# PCB.net
KiCad netlist of a schematic drawn in EAGLE
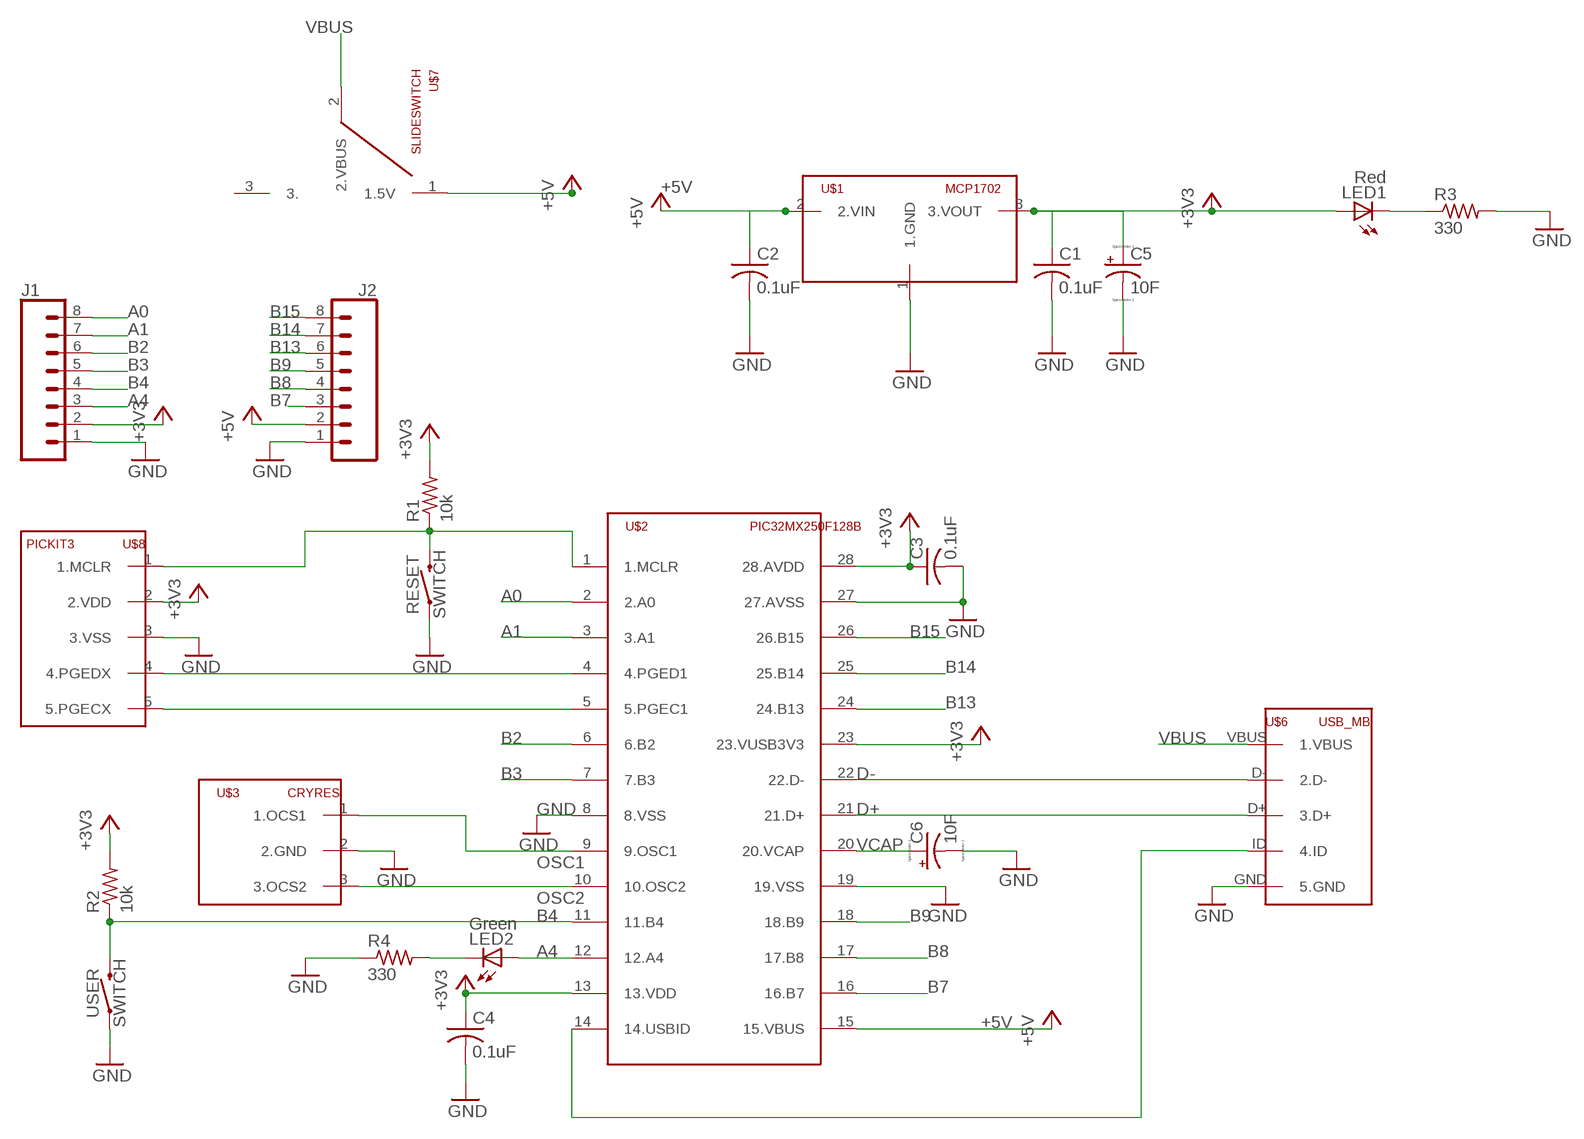
[diagram p0: schematic, sheet 1]

(export (version "E")
  (design (tool "Eeschema 10.0.6"))
  (components
    (comp (ref "C1")
      (value "0.1uF")
      (footprint "eagle-import:C025-025X050")
      (libsource (lib "eagle-import") (part "C-US025-025X050"))
    )
    (comp (ref "C2")
      (value "0.1uF")
      (footprint "eagle-import:C025-025X050")
      (libsource (lib "eagle-import") (part "C-US025-025X050"))
    )
    (comp (ref "C3")
      (value "0.1uF")
      (footprint "eagle-import:C025-025X050")
      (libsource (lib "eagle-import") (part "C-US025-025X050"))
    )
    (comp (ref "C4")
      (value "0.1uF")
      (footprint "eagle-import:C025-025X050")
      (libsource (lib "eagle-import") (part "C-US025-025X050"))
    )
    (comp (ref "C5")
      (value "10F")
      (footprint "eagle-import:E5-5")
      (libsource (lib "eagle-import") (part "CPOL-USE5-5"))
    )
    (comp (ref "C6")
      (value "10F")
      (footprint "eagle-import:E5-5")
      (libsource (lib "eagle-import") (part "CPOL-USE5-5"))
    )
    (comp (ref "J1")
      (value "CONN_08\"")
      (footprint "eagle-import:1X08")
      (libsource (lib "eagle-import") (part "CONN_08{dblquote}"))
    )
    (comp (ref "J2")
      (value "CONN_08\"")
      (footprint "eagle-import:1X08")
      (libsource (lib "eagle-import") (part "CONN_08{dblquote}"))
    )
    (comp (ref "LED1")
      (value "Red")
      (footprint "eagle-import:LED3MM")
      (libsource (lib "eagle-import") (part "LED3MM"))
    )
    (comp (ref "LED2")
      (value "Green")
      (footprint "eagle-import:LED3MM")
      (libsource (lib "eagle-import") (part "LED3MM"))
    )
    (comp (ref "R1")
      (value "10k")
      (footprint "eagle-import:0207_10")
      (libsource (lib "eagle-import") (part "R-US_0207/10"))
    )
    (comp (ref "R2")
      (value "10k")
      (footprint "eagle-import:0207_10")
      (libsource (lib "eagle-import") (part "R-US_0207/10"))
    )
    (comp (ref "R3")
      (value "330")
      (footprint "eagle-import:0207_10")
      (libsource (lib "eagle-import") (part "R-US_0207/10"))
    )
    (comp (ref "R4")
      (value "330")
      (footprint "eagle-import:0207_10")
      (libsource (lib "eagle-import") (part "R-US_0207/10"))
    )
    (comp (ref "RESET")
      (value "SWITCH")
      (footprint "eagle-import:SWITCH")
      (libsource (lib "eagle-import") (part "SWITCH"))
    )
    (comp (ref "U$1")
      (value "MCP1702")
      (footprint "eagle-import:TO92")
      (libsource (lib "eagle-import") (part "MCP1702"))
    )
    (comp (ref "U$2")
      (value "PIC32MX250F128B")
      (footprint "eagle-import:DIL28-3")
      (libsource (lib "eagle-import") (part "PIC32MX250F128B"))
    )
    (comp (ref "U$3")
      (value "CRYRES")
      (footprint "eagle-import:CRYSTAL")
      (libsource (lib "eagle-import") (part "CRYRES"))
    )
    (comp (ref "U$6")
      (value "USB_MB")
      (footprint "eagle-import:USB-MB-H")
      (libsource (lib "eagle-import") (part "USB_MB"))
    )
    (comp (ref "U$7")
      (value "SLIDESWITCH")
      (footprint "eagle-import:SLIDESWITCH")
      (libsource (lib "eagle-import") (part "SLIDESWITCH"))
    )
    (comp (ref "U$8")
      (value "PICKIT3")
      (footprint "eagle-import:1X05")
      (libsource (lib "eagle-import") (part "PICKIT3"))
    )
    (comp (ref "USER")
      (value "SWITCH")
      (footprint "eagle-import:SWITCH")
      (libsource (lib "eagle-import") (part "SWITCH"))
    )
  )
  (nets
    (net (code "1") (name "+3V3") (class "Default")
      (node (ref "C1") (pin "1") (pinfunction "1_1") (pintype "passive"))
      (node (ref "C3") (pin "1") (pinfunction "1_1") (pintype "passive"))
      (node (ref "C4") (pin "1") (pinfunction "1_1") (pintype "passive"))
      (node (ref "C5") (pin "+") (pinfunction "+_+") (pintype "passive"))
      (node (ref "J1") (pin "2") (pinfunction "2_2") (pintype "passive"))
      (node (ref "LED1") (pin "A") (pinfunction "A_A") (pintype "passive"))
      (node (ref "R1") (pin "2") (pinfunction "2_2") (pintype "passive"))
      (node (ref "R2") (pin "2") (pinfunction "2_2") (pintype "passive"))
      (node (ref "U$1") (pin "3") (pinfunction "3.VOUT_3") (pintype "bidirectional"))
      (node (ref "U$2") (pin "13") (pinfunction "13.VDD_13") (pintype "bidirectional"))
      (node (ref "U$2") (pin "23") (pinfunction "23.VUSB3V3_23") (pintype "bidirectional"))
      (node (ref "U$2") (pin "28") (pinfunction "28.AVDD_28") (pintype "bidirectional"))
      (node (ref "U$8") (pin "2") (pinfunction "2.VDD_2") (pintype "bidirectional"))
    )
    (net (code "2") (name "+5V") (class "Default")
      (node (ref "C2") (pin "1") (pinfunction "1_1") (pintype "passive"))
      (node (ref "J2") (pin "2") (pinfunction "2_2") (pintype "passive"))
      (node (ref "U$1") (pin "2") (pinfunction "2.VIN_2") (pintype "bidirectional"))
      (node (ref "U$2") (pin "15") (pinfunction "15.VBUS_15") (pintype "bidirectional"))
      (node (ref "U$7") (pin "1") (pinfunction "1.5V_1") (pintype "bidirectional"))
    )
    (net (code "3") (name "/A0") (class "Default")
      (node (ref "J1") (pin "8") (pinfunction "8_8") (pintype "passive"))
      (node (ref "U$2") (pin "2") (pinfunction "2.A0_2") (pintype "bidirectional"))
    )
    (net (code "4") (name "/A1") (class "Default")
      (node (ref "J1") (pin "7") (pinfunction "7_7") (pintype "passive"))
      (node (ref "U$2") (pin "3") (pinfunction "3.A1_3") (pintype "bidirectional"))
    )
    (net (code "5") (name "/A4") (class "Default")
      (node (ref "J1") (pin "3") (pinfunction "3_3") (pintype "passive"))
      (node (ref "LED2") (pin "A") (pinfunction "A_A") (pintype "passive"))
      (node (ref "U$2") (pin "12") (pinfunction "12.A4_12") (pintype "bidirectional"))
    )
    (net (code "6") (name "/B2") (class "Default")
      (node (ref "J1") (pin "6") (pinfunction "6_6") (pintype "passive"))
      (node (ref "U$2") (pin "6") (pinfunction "6.B2_6") (pintype "bidirectional"))
    )
    (net (code "7") (name "/B3") (class "Default")
      (node (ref "J1") (pin "5") (pinfunction "5_5") (pintype "passive"))
      (node (ref "U$2") (pin "7") (pinfunction "7.B3_7") (pintype "bidirectional"))
    )
    (net (code "8") (name "/B4") (class "Default")
      (node (ref "J1") (pin "4") (pinfunction "4_4") (pintype "passive"))
      (node (ref "R2") (pin "1") (pinfunction "1_1") (pintype "passive"))
      (node (ref "U$2") (pin "11") (pinfunction "11.B4_11") (pintype "bidirectional"))
      (node (ref "USER") (pin "2") (pinfunction "2_2") (pintype "passive"))
    )
    (net (code "9") (name "/B7") (class "Default")
      (node (ref "J2") (pin "3") (pinfunction "3_3") (pintype "passive"))
      (node (ref "U$2") (pin "16") (pinfunction "16.B7_16") (pintype "bidirectional"))
    )
    (net (code "10") (name "/B8") (class "Default")
      (node (ref "J2") (pin "4") (pinfunction "4_4") (pintype "passive"))
      (node (ref "U$2") (pin "17") (pinfunction "17.B8_17") (pintype "bidirectional"))
    )
    (net (code "11") (name "/B9") (class "Default")
      (node (ref "J2") (pin "5") (pinfunction "5_5") (pintype "passive"))
      (node (ref "U$2") (pin "18") (pinfunction "18.B9_18") (pintype "bidirectional"))
    )
    (net (code "12") (name "/B13") (class "Default")
      (node (ref "J2") (pin "6") (pinfunction "6_6") (pintype "passive"))
      (node (ref "U$2") (pin "24") (pinfunction "24.B13_24") (pintype "bidirectional"))
    )
    (net (code "13") (name "/B14") (class "Default")
      (node (ref "J2") (pin "7") (pinfunction "7_7") (pintype "passive"))
      (node (ref "U$2") (pin "25") (pinfunction "25.B14_25") (pintype "bidirectional"))
    )
    (net (code "14") (name "/B15") (class "Default")
      (node (ref "J2") (pin "8") (pinfunction "8_8") (pintype "passive"))
      (node (ref "U$2") (pin "26") (pinfunction "26.B15_26") (pintype "bidirectional"))
    )
    (net (code "15") (name "/D+") (class "Default")
      (node (ref "U$2") (pin "21") (pinfunction "21.D+_21") (pintype "bidirectional"))
      (node (ref "U$6") (pin "D+") (pinfunction "3.D+_D+") (pintype "bidirectional"))
    )
    (net (code "16") (name "/D-") (class "Default")
      (node (ref "U$2") (pin "22") (pinfunction "22.D-_22") (pintype "bidirectional"))
      (node (ref "U$6") (pin "D-") (pinfunction "2.D-_D-") (pintype "bidirectional"))
    )
    (net (code "17") (name "/OSC1") (class "Default")
      (node (ref "U$2") (pin "9") (pinfunction "9.OSC1_9") (pintype "bidirectional"))
      (node (ref "U$3") (pin "1") (pinfunction "1.OCS1_1") (pintype "bidirectional"))
    )
    (net (code "18") (name "/OSC2") (class "Default")
      (node (ref "U$2") (pin "10") (pinfunction "10.OSC2_10") (pintype "bidirectional"))
      (node (ref "U$3") (pin "3") (pinfunction "3.OCS2_3") (pintype "bidirectional"))
    )
    (net (code "19") (name "/VBUS") (class "Default")
      (node (ref "U$6") (pin "VBUS") (pinfunction "1.VBUS_VBUS") (pintype "bidirectional"))
      (node (ref "U$7") (pin "2") (pinfunction "2.VBUS_2") (pintype "bidirectional"))
    )
    (net (code "20") (name "/VCAP") (class "Default")
      (node (ref "C6") (pin "+") (pinfunction "+_+") (pintype "passive"))
      (node (ref "U$2") (pin "20") (pinfunction "20.VCAP_20") (pintype "bidirectional"))
    )
    (net (code "21") (name "GND") (class "Default")
      (node (ref "C1") (pin "2") (pinfunction "2_2") (pintype "passive"))
      (node (ref "C2") (pin "2") (pinfunction "2_2") (pintype "passive"))
      (node (ref "C3") (pin "2") (pinfunction "2_2") (pintype "passive"))
      (node (ref "C4") (pin "2") (pinfunction "2_2") (pintype "passive"))
      (node (ref "C5") (pin "-") (pinfunction "-_-") (pintype "passive"))
      (node (ref "C6") (pin "-") (pinfunction "-_-") (pintype "passive"))
      (node (ref "J1") (pin "1") (pinfunction "1_1") (pintype "passive"))
      (node (ref "J2") (pin "1") (pinfunction "1_1") (pintype "passive"))
      (node (ref "R3") (pin "2") (pinfunction "2_2") (pintype "passive"))
      (node (ref "R4") (pin "1") (pinfunction "1_1") (pintype "passive"))
      (node (ref "RESET") (pin "1") (pinfunction "1_1") (pintype "passive"))
      (node (ref "U$1") (pin "1") (pinfunction "1.GND_1") (pintype "bidirectional"))
      (node (ref "U$2") (pin "19") (pinfunction "19.VSS_19") (pintype "bidirectional"))
      (node (ref "U$2") (pin "27") (pinfunction "27.AVSS_27") (pintype "bidirectional"))
      (node (ref "U$2") (pin "8") (pinfunction "8.VSS_8") (pintype "bidirectional"))
      (node (ref "U$3") (pin "2") (pinfunction "2.GND_2") (pintype "bidirectional"))
      (node (ref "U$6") (pin "GND") (pinfunction "5.GND_GND") (pintype "bidirectional"))
      (node (ref "U$8") (pin "3") (pinfunction "3.VSS_3") (pintype "bidirectional"))
      (node (ref "USER") (pin "1") (pinfunction "1_1") (pintype "passive"))
    )
    (net (code "22") (name "Net-(LED1-C)") (class "Default")
      (node (ref "LED1") (pin "K") (pinfunction "C_K") (pintype "passive"))
      (node (ref "R3") (pin "1") (pinfunction "1_1") (pintype "passive"))
    )
    (net (code "23") (name "Net-(LED2-C)") (class "Default")
      (node (ref "LED2") (pin "K") (pinfunction "C_K") (pintype "passive"))
      (node (ref "R4") (pin "2") (pinfunction "2_2") (pintype "passive"))
    )
    (net (code "24") (name "Net-(U$2-1.MCLR)") (class "Default")
      (node (ref "R1") (pin "1") (pinfunction "1_1") (pintype "passive"))
      (node (ref "RESET") (pin "2") (pinfunction "2_2") (pintype "passive"))
      (node (ref "U$2") (pin "1") (pinfunction "1.MCLR_1") (pintype "bidirectional"))
      (node (ref "U$8") (pin "1") (pinfunction "1.MCLR_1") (pintype "bidirectional"))
    )
    (net (code "25") (name "Net-(U$2-4.PGED1)") (class "Default")
      (node (ref "U$2") (pin "4") (pinfunction "4.PGED1_4") (pintype "bidirectional"))
      (node (ref "U$8") (pin "4") (pinfunction "4.PGEDX_4") (pintype "bidirectional"))
    )
    (net (code "26") (name "Net-(U$2-5.PGEC1)") (class "Default")
      (node (ref "U$2") (pin "5") (pinfunction "5.PGEC1_5") (pintype "bidirectional"))
      (node (ref "U$8") (pin "5") (pinfunction "5.PGECX_5") (pintype "bidirectional"))
    )
    (net (code "27") (name "Net-(U$2-14.USBID)") (class "Default")
      (node (ref "U$2") (pin "14") (pinfunction "14.USBID_14") (pintype "bidirectional"))
      (node (ref "U$6") (pin "ID") (pinfunction "4.ID_ID") (pintype "bidirectional"))
    )
    (net (code "28") (name "unconnected-(U$7-3.-Pad3)") (class "Default")
      (node (ref "U$7") (pin "3") (pinfunction "3._3") (pintype "bidirectional"))
    )
  )
)
